# Clone.net
KiCad netlist of a schematic drawn in EAGLE
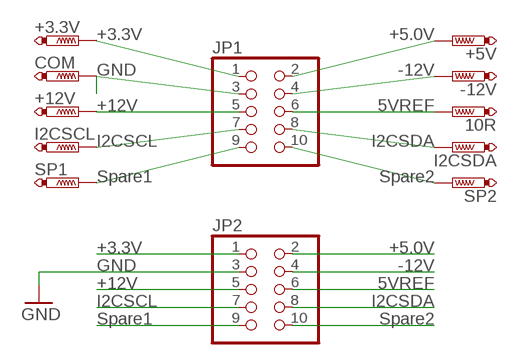
[diagram p0: schematic, sheet 1]

(export (version "E")
  (design (tool "Eeschema 10.0.6"))
  (components
    (comp (ref "+3.3V")
      (value "PTR1B1,27")
      (footprint "eagle-import:B1,27")
      (libsource (lib "eagle-import") (part "PTR1B1,27"))
    )
    (comp (ref "+5V")
      (value "PTR1B1,27")
      (footprint "eagle-import:B1,27")
      (libsource (lib "eagle-import") (part "PTR1B1,27"))
    )
    (comp (ref "+12V")
      (value "PTR1B1,27")
      (footprint "eagle-import:B1,27")
      (libsource (lib "eagle-import") (part "PTR1B1,27"))
    )
    (comp (ref "-12V")
      (value "PTR1B1,27")
      (footprint "eagle-import:B1,27")
      (libsource (lib "eagle-import") (part "PTR1B1,27"))
    )
    (comp (ref "10R")
      (value "PTR1B1,27")
      (footprint "eagle-import:B1,27")
      (libsource (lib "eagle-import") (part "PTR1B1,27"))
    )
    (comp (ref "COM")
      (value "PTR1B1,27")
      (footprint "eagle-import:B1,27")
      (libsource (lib "eagle-import") (part "PTR1B1,27"))
    )
    (comp (ref "I2CSCL")
      (value "PTR1B1,27")
      (footprint "eagle-import:B1,27")
      (libsource (lib "eagle-import") (part "PTR1B1,27"))
    )
    (comp (ref "I2CSDA")
      (value "PTR1B1,27")
      (footprint "eagle-import:B1,27")
      (libsource (lib "eagle-import") (part "PTR1B1,27"))
    )
    (comp (ref "JP1")
      (value "PINHD-2X5/90")
      (footprint "eagle-import:2X05_90")
      (libsource (lib "eagle-import") (part "PINHD-2X5/90"))
    )
    (comp (ref "JP2")
      (value "PINHD-2X5/90")
      (footprint "eagle-import:2X05_90")
      (libsource (lib "eagle-import") (part "PINHD-2X5/90"))
    )
    (comp (ref "SP1")
      (value "PTR1B1,27")
      (footprint "eagle-import:B1,27")
      (libsource (lib "eagle-import") (part "PTR1B1,27"))
    )
    (comp (ref "SP2")
      (value "PTR1B1,27")
      (footprint "eagle-import:B1,27")
      (libsource (lib "eagle-import") (part "PTR1B1,27"))
    )
  )
  (nets
    (net (code "1") (name "/+3.3V") (class "Default")
      (node (ref "+3.3V") (pin "TP") (pinfunction "TP_TP") (pintype "input"))
      (node (ref "JP1") (pin "1") (pinfunction "1_1") (pintype "passive"))
      (node (ref "JP2") (pin "1") (pinfunction "1_1") (pintype "passive"))
    )
    (net (code "2") (name "/+5.0V") (class "Default")
      (node (ref "+5V") (pin "TP") (pinfunction "TP_TP") (pintype "input"))
      (node (ref "JP1") (pin "2") (pinfunction "2_2") (pintype "passive"))
      (node (ref "JP2") (pin "2") (pinfunction "2_2") (pintype "passive"))
    )
    (net (code "3") (name "/+12V") (class "Default")
      (node (ref "+12V") (pin "TP") (pinfunction "TP_TP") (pintype "input"))
      (node (ref "JP1") (pin "5") (pinfunction "5_5") (pintype "passive"))
      (node (ref "JP2") (pin "5") (pinfunction "5_5") (pintype "passive"))
    )
    (net (code "4") (name "/-12V") (class "Default")
      (node (ref "-12V") (pin "TP") (pinfunction "TP_TP") (pintype "input"))
      (node (ref "JP1") (pin "4") (pinfunction "4_4") (pintype "passive"))
      (node (ref "JP2") (pin "4") (pinfunction "4_4") (pintype "passive"))
    )
    (net (code "5") (name "/5VREF") (class "Default")
      (node (ref "10R") (pin "TP") (pinfunction "TP_TP") (pintype "input"))
      (node (ref "JP1") (pin "6") (pinfunction "6_6") (pintype "passive"))
      (node (ref "JP2") (pin "6") (pinfunction "6_6") (pintype "passive"))
    )
    (net (code "6") (name "/I2CSCL") (class "Default")
      (node (ref "I2CSCL") (pin "TP") (pinfunction "TP_TP") (pintype "input"))
      (node (ref "JP1") (pin "7") (pinfunction "7_7") (pintype "passive"))
      (node (ref "JP2") (pin "7") (pinfunction "7_7") (pintype "passive"))
    )
    (net (code "7") (name "/I2CSDA") (class "Default")
      (node (ref "I2CSDA") (pin "TP") (pinfunction "TP_TP") (pintype "input"))
      (node (ref "JP1") (pin "8") (pinfunction "8_8") (pintype "passive"))
      (node (ref "JP2") (pin "8") (pinfunction "8_8") (pintype "passive"))
    )
    (net (code "8") (name "/SPARE1") (class "Default")
      (node (ref "JP1") (pin "9") (pinfunction "9_9") (pintype "passive"))
      (node (ref "JP2") (pin "9") (pinfunction "9_9") (pintype "passive"))
      (node (ref "SP1") (pin "TP") (pinfunction "TP_TP") (pintype "input"))
    )
    (net (code "9") (name "/SPARE2") (class "Default")
      (node (ref "JP1") (pin "10") (pinfunction "10_10") (pintype "passive"))
      (node (ref "JP2") (pin "10") (pinfunction "10_10") (pintype "passive"))
      (node (ref "SP2") (pin "TP") (pinfunction "TP_TP") (pintype "input"))
    )
    (net (code "10") (name "GND") (class "Default")
      (node (ref "COM") (pin "TP") (pinfunction "TP_TP") (pintype "input"))
      (node (ref "JP1") (pin "3") (pinfunction "3_3") (pintype "passive"))
      (node (ref "JP2") (pin "3") (pinfunction "3_3") (pintype "passive"))
    )
  )
)
